# HackmodWear_hexagonSensor.net
KiCad netlist of a schematic drawn in EAGLE
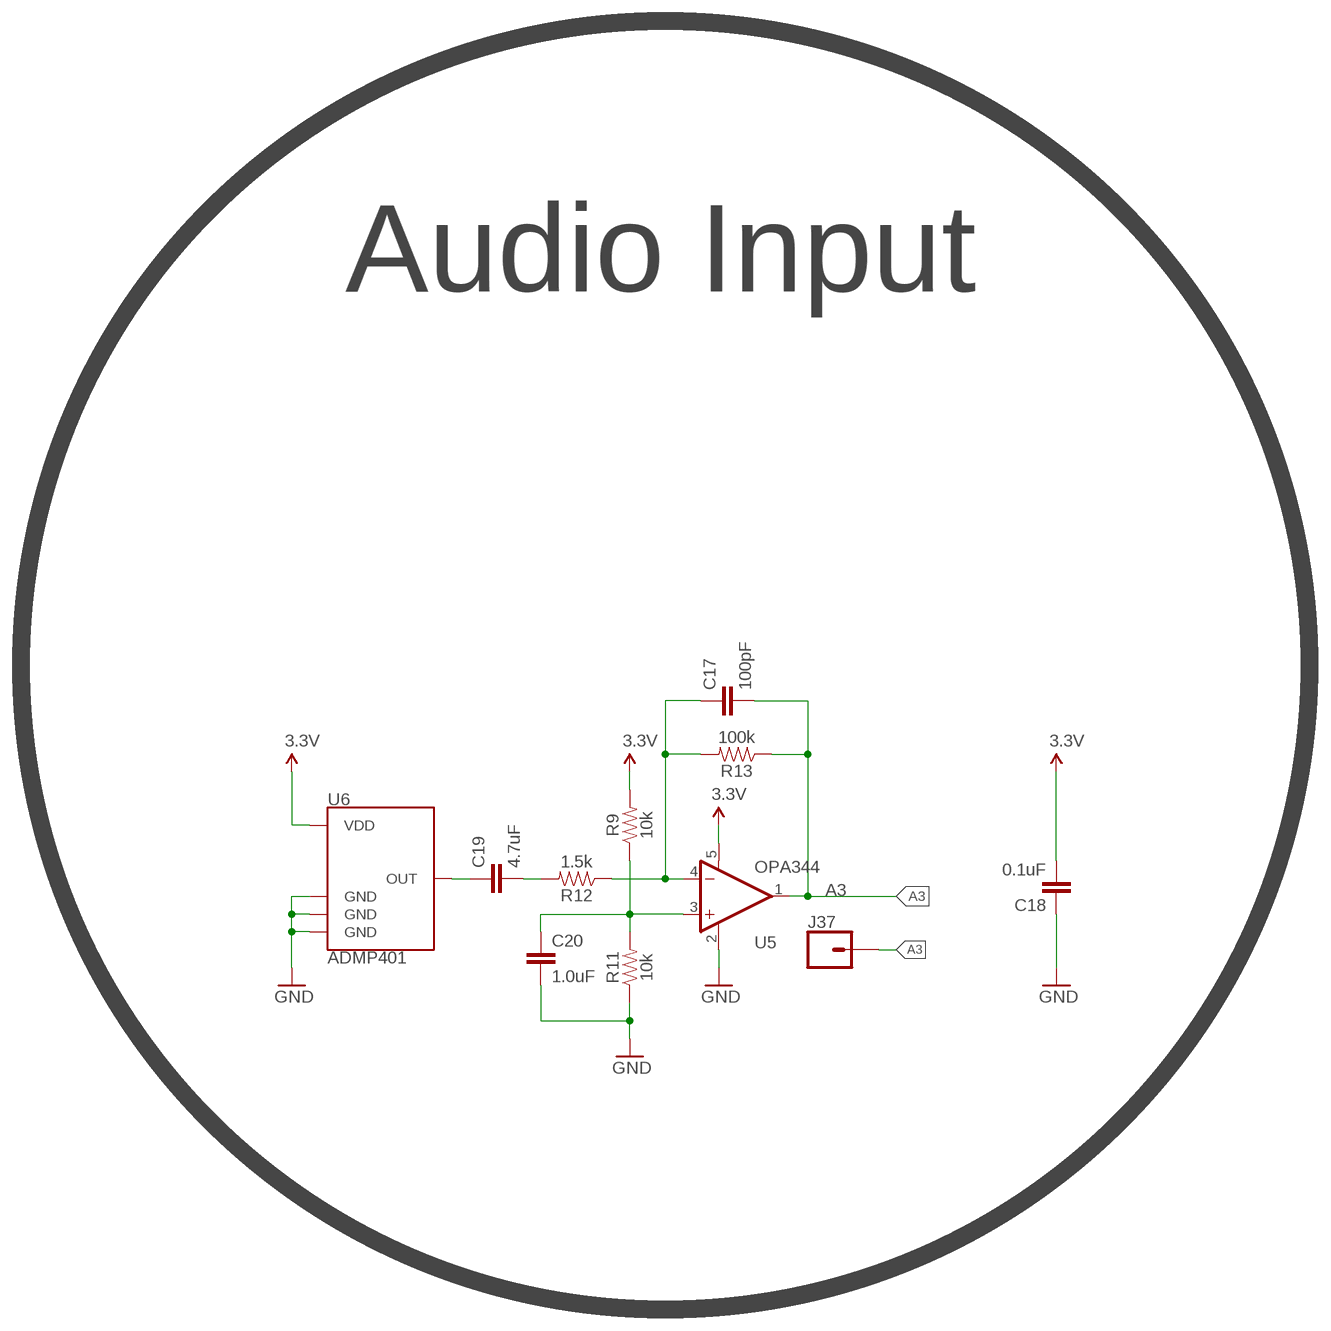
[diagram p0: schematic, sheet 1, part 1 of 2]
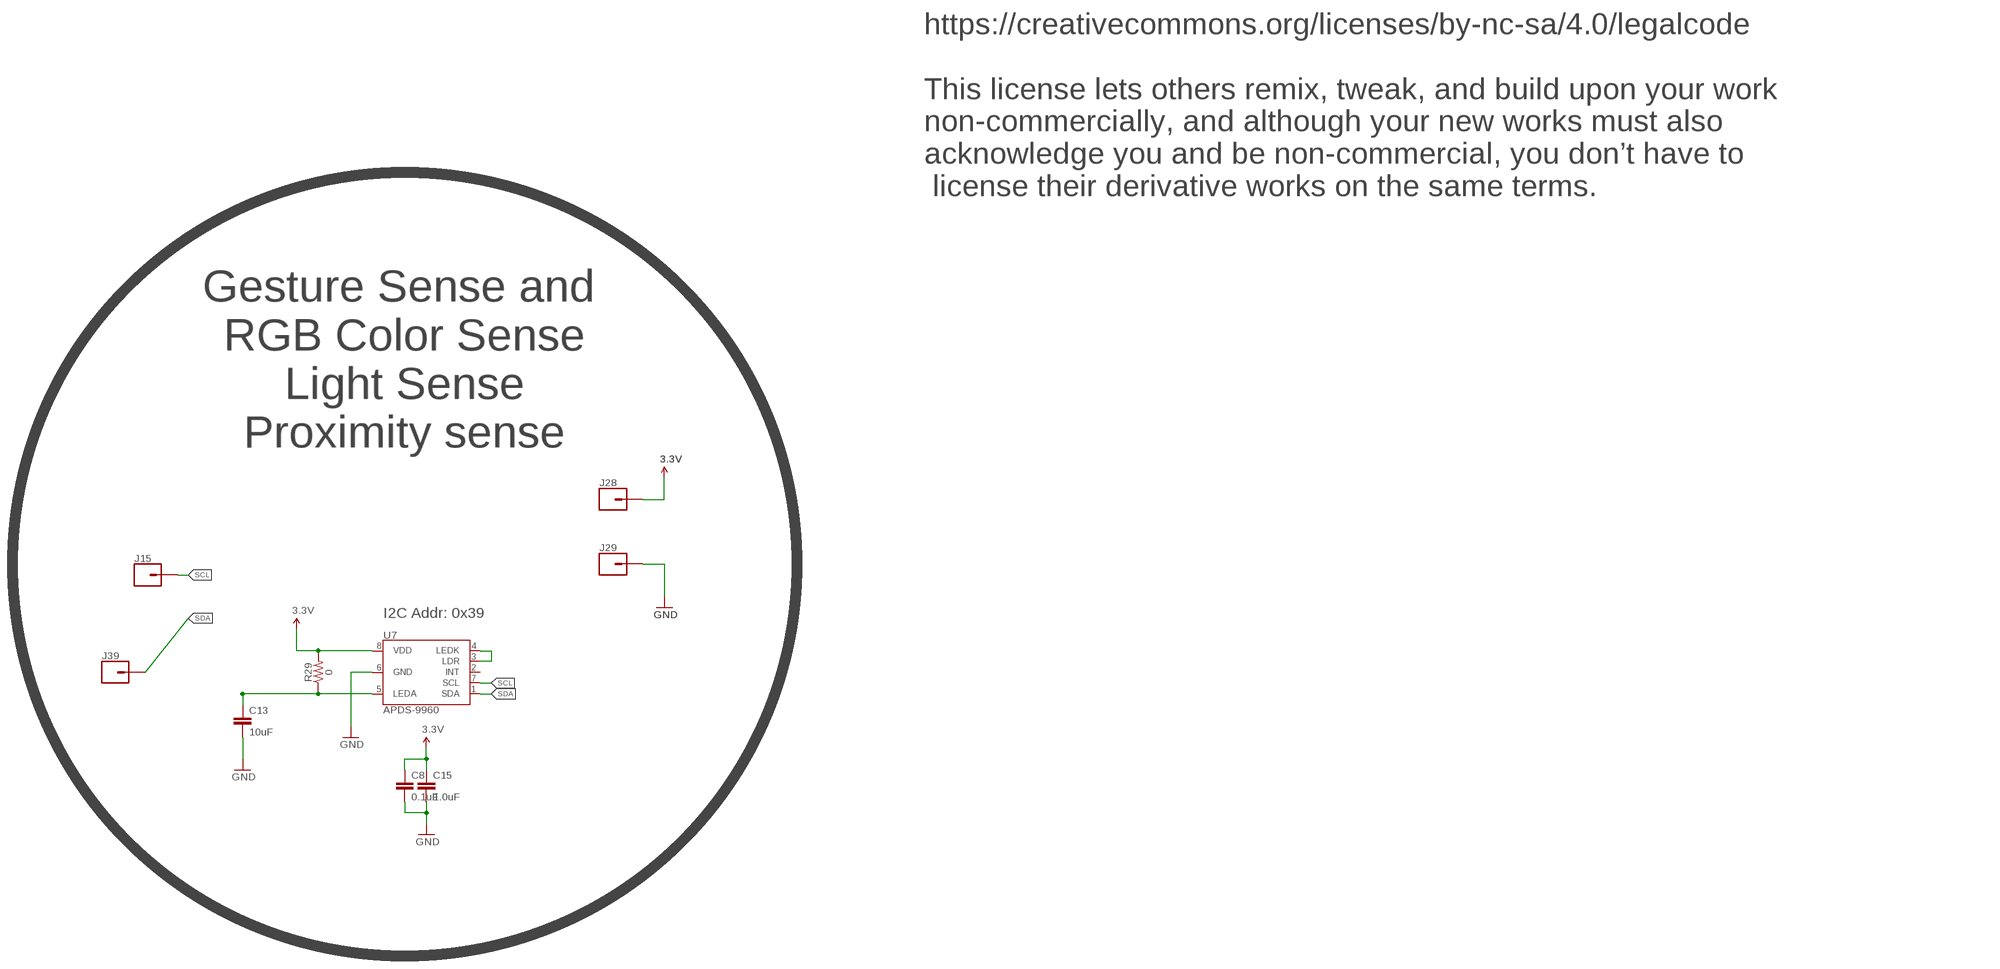
[diagram p1: schematic, sheet 1, part 2 of 2]

(export (version "E")
  (design (tool "Eeschema 10.0.6"))
  (components
    (comp (ref "C8")
      (value "0.1uF")
      (footprint "eagle-import:0603")
      (libsource (lib "eagle-import") (part "0.1UF-0603-25V-(+80/-20%)"))
    )
    (comp (ref "C13")
      (value "10uF")
      (footprint "eagle-import:0805")
      (libsource (lib "eagle-import") (part "10UF-0805-10V-10%"))
    )
    (comp (ref "C15")
      (value "1.0uF")
      (footprint "eagle-import:0603")
      (libsource (lib "eagle-import") (part "1.0UF-0603-16V-10%"))
    )
    (comp (ref "C17")
      (value "100pF")
      (footprint "eagle-import:0603")
      (libsource (lib "eagle-import") (part "100PF-0603-50V-5%"))
    )
    (comp (ref "C18")
      (value "0.1uF")
      (footprint "eagle-import:0603")
      (libsource (lib "eagle-import") (part "0.1UF-0603-25V-(+80/-20%)"))
    )
    (comp (ref "C19")
      (value "4.7uF")
      (footprint "eagle-import:0603")
      (libsource (lib "eagle-import") (part "4.7UF-0603-6.3V-(10%)"))
    )
    (comp (ref "C20")
      (value "1.0uF")
      (footprint "eagle-import:0603")
      (libsource (lib "eagle-import") (part "1.0UF-0603-16V-10%"))
    )
    (comp (ref "J15")
      (value "CONN_01")
      (footprint "eagle-import:1X01")
      (libsource (lib "eagle-import") (part "CONN_01"))
    )
    (comp (ref "J28")
      (value "CONN_01")
      (footprint "eagle-import:1X01")
      (libsource (lib "eagle-import") (part "CONN_01"))
    )
    (comp (ref "J29")
      (value "CONN_01")
      (footprint "eagle-import:1X01")
      (libsource (lib "eagle-import") (part "CONN_01"))
    )
    (comp (ref "J37")
      (value "CONN_01")
      (footprint "eagle-import:1X01")
      (libsource (lib "eagle-import") (part "CONN_01"))
    )
    (comp (ref "J39")
      (value "CONN_01")
      (footprint "eagle-import:1X01")
      (libsource (lib "eagle-import") (part "CONN_01"))
    )
    (comp (ref "R9")
      (value "10k")
      (footprint "eagle-import:0603")
      (libsource (lib "eagle-import") (part "10KOHM-0603-1/10W-1%"))
    )
    (comp (ref "R11")
      (value "10k")
      (footprint "eagle-import:0603")
      (libsource (lib "eagle-import") (part "10KOHM-0603-1/10W-1%"))
    )
    (comp (ref "R12")
      (value "1.5k")
      (footprint "eagle-import:0603")
      (libsource (lib "eagle-import") (part "1.5KOHM-0603-1/10W-1%"))
    )
    (comp (ref "R13")
      (value "100k")
      (footprint "eagle-import:0603")
      (libsource (lib "eagle-import") (part "100KOHM-0603-1/10W-1%"))
    )
    (comp (ref "R29")
      (value "0")
      (footprint "eagle-import:0603")
      (libsource (lib "eagle-import") (part "0OHM-0603-1/10W-5%"))
    )
    (comp (ref "U5")
      (value "OPA344")
      (footprint "eagle-import:SOT23-5")
      (libsource (lib "eagle-import") (part "OPA344"))
    )
    (comp (ref "U6")
      (value "ADMP401")
      (footprint "eagle-import:ADMP401")
      (libsource (lib "eagle-import") (part "ADMP401"))
    )
    (comp (ref "U7")
      (value "APDS-9960")
      (footprint "eagle-import:APDS-9960")
      (libsource (lib "eagle-import") (part "APDS-9960"))
    )
  )
  (nets
    (net (code "1") (name "3.3V") (class "Default")
      (node (ref "C15") (pin "1") (pinfunction "1_1") (pintype "passive"))
      (node (ref "C18") (pin "2") (pinfunction "2_2") (pintype "passive"))
      (node (ref "C8") (pin "1") (pinfunction "1_1") (pintype "passive"))
      (node (ref "J28") (pin "P$1") (pinfunction "1_P$1") (pintype "passive"))
      (node (ref "R29") (pin "2") (pinfunction "2_2") (pintype "passive"))
      (node (ref "R9") (pin "2") (pinfunction "2_2") (pintype "passive"))
      (node (ref "U5") (pin "5") (pinfunction "V+_5") (pintype "power_in"))
      (node (ref "U6") (pin "5") (pinfunction "VDD_5") (pintype "bidirectional"))
      (node (ref "U7") (pin "8") (pinfunction "VDD_8") (pintype "bidirectional"))
    )
    (net (code "2") (name "A3") (class "Default")
      (node (ref "C17") (pin "2") (pinfunction "2_2") (pintype "passive"))
      (node (ref "J37") (pin "P$1") (pinfunction "1_P$1") (pintype "passive"))
      (node (ref "R13") (pin "1") (pinfunction "1_1") (pintype "passive"))
      (node (ref "U5") (pin "1") (pinfunction "OUT_1") (pintype "output"))
    )
    (net (code "3") (name "GND") (class "Default")
      (node (ref "C13") (pin "2") (pinfunction "2_2") (pintype "passive"))
      (node (ref "C15") (pin "2") (pinfunction "2_2") (pintype "passive"))
      (node (ref "C18") (pin "1") (pinfunction "1_1") (pintype "passive"))
      (node (ref "C20") (pin "2") (pinfunction "2_2") (pintype "passive"))
      (node (ref "C8") (pin "2") (pinfunction "2_2") (pintype "passive"))
      (node (ref "J29") (pin "P$1") (pinfunction "1_P$1") (pintype "passive"))
      (node (ref "R11") (pin "1") (pinfunction "1_1") (pintype "passive"))
      (node (ref "U5") (pin "2") (pinfunction "V-_2") (pintype "power_in"))
      (node (ref "U6") (pin "2") (pinfunction "GND_2") (pintype "bidirectional"))
      (node (ref "U6") (pin "4") (pinfunction "GND_4") (pintype "bidirectional"))
      (node (ref "U6") (pin "6") (pinfunction "GND_6") (pintype "bidirectional"))
      (node (ref "U7") (pin "6") (pinfunction "GND_6") (pintype "bidirectional"))
    )
    (net (code "4") (name "Net-(C19-Pad2)") (class "Default")
      (node (ref "C19") (pin "2") (pinfunction "2_2") (pintype "passive"))
      (node (ref "R12") (pin "2") (pinfunction "2_2") (pintype "passive"))
    )
    (net (code "5") (name "Net-(U5-+IN)") (class "Default")
      (node (ref "C20") (pin "1") (pinfunction "1_1") (pintype "passive"))
      (node (ref "R11") (pin "2") (pinfunction "2_2") (pintype "passive"))
      (node (ref "R9") (pin "1") (pinfunction "1_1") (pintype "passive"))
      (node (ref "U5") (pin "3") (pinfunction "+IN_3") (pintype "input"))
    )
    (net (code "6") (name "Net-(U5--IN)") (class "Default")
      (node (ref "C17") (pin "1") (pinfunction "1_1") (pintype "passive"))
      (node (ref "R12") (pin "1") (pinfunction "1_1") (pintype "passive"))
      (node (ref "R13") (pin "2") (pinfunction "2_2") (pintype "passive"))
      (node (ref "U5") (pin "4") (pinfunction "-IN_4") (pintype "input"))
    )
    (net (code "7") (name "Net-(U6-OUT)") (class "Default")
      (node (ref "C19") (pin "1") (pinfunction "1_1") (pintype "passive"))
      (node (ref "U6") (pin "1") (pinfunction "OUT_1") (pintype "bidirectional"))
    )
    (net (code "8") (name "Net-(U7-LDR)") (class "Default")
      (node (ref "U7") (pin "3") (pinfunction "LDR_3") (pintype "bidirectional"))
      (node (ref "U7") (pin "4") (pinfunction "LEDK_4") (pintype "bidirectional"))
    )
    (net (code "9") (name "Net-(U7-LEDA)") (class "Default")
      (node (ref "C13") (pin "1") (pinfunction "1_1") (pintype "passive"))
      (node (ref "R29") (pin "1") (pinfunction "1_1") (pintype "passive"))
      (node (ref "U7") (pin "5") (pinfunction "LEDA_5") (pintype "bidirectional"))
    )
    (net (code "10") (name "SCL") (class "Default")
      (node (ref "J15") (pin "P$1") (pinfunction "1_P$1") (pintype "passive"))
      (node (ref "U7") (pin "7") (pinfunction "SCL_7") (pintype "bidirectional"))
    )
    (net (code "11") (name "SDA") (class "Default")
      (node (ref "J39") (pin "P$1") (pinfunction "1_P$1") (pintype "passive"))
      (node (ref "U7") (pin "1") (pinfunction "SDA_1") (pintype "bidirectional"))
    )
    (net (code "12") (name "unconnected-(U7-INT-Pad2)") (class "Default")
      (node (ref "U7") (pin "2") (pinfunction "INT_2") (pintype "bidirectional"))
    )
  )
)
